# 7_Solenoid.net
KiCad netlist of a schematic drawn in Altium Designer
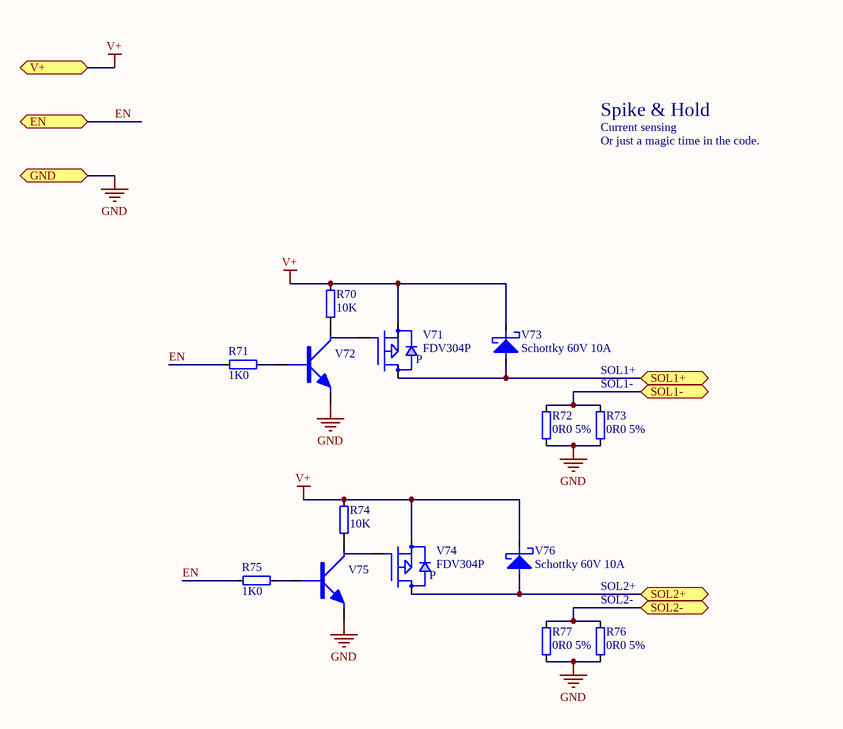
[diagram p0: 7_Solenoid.SchDoc]

(export (version "E")
  (design (tool "Eeschema 10.0.6"))
  (components
    (comp (ref "R70")
      (value "10K")
      (footprint "1206")
      (description "Resistor")
      (fields
        (field (name "MANUFACTURER") "Phycomp")
        (field (name "PARTNUMBER") "RC1206FR-0710KL")
        (field (name "CHECKEDBY") "ART")
      )
      (libsource (lib "SVN_BOMGEN_Database_2014") (part "RES"))
    )
    (comp (ref "R71")
      (value "1K0")
      (footprint "0805")
      (description "Resistor")
      (fields
        (field (name "MANUFACTURER") "Phycomp")
        (field (name "PARTNUMBER") "RC0805FR-071KL")
        (field (name "CHECKEDBY") "ART")
      )
      (libsource (lib "SVN_BOMGEN_Database_2014") (part "RES"))
    )
    (comp (ref "R72")
      (value "0R0 5%")
      (footprint "1206")
      (description "Resistor")
      (fields
        (field (name "MANUFACTURER") "Phycomp")
        (field (name "PARTNUMBER") "RC1206JR-070RL")
        (field (name "CHECKEDBY") "ART")
      )
      (libsource (lib "SVN_BOMGEN_Database_2014") (part "RES"))
    )
    (comp (ref "R73")
      (value "0R0 5%")
      (footprint "1206")
      (description "Resistor")
      (fields
        (field (name "MANUFACTURER") "Phycomp")
        (field (name "PARTNUMBER") "RC1206JR-070RL")
        (field (name "CHECKEDBY") "ART")
      )
      (libsource (lib "SVN_BOMGEN_Database_2014") (part "RES"))
    )
    (comp (ref "R74")
      (value "10K")
      (footprint "1206")
      (description "Resistor")
      (fields
        (field (name "MANUFACTURER") "Phycomp")
        (field (name "PARTNUMBER") "RC1206FR-0710KL")
        (field (name "CHECKEDBY") "ART")
      )
      (libsource (lib "SVN_BOMGEN_Database_2014") (part "RES"))
    )
    (comp (ref "R75")
      (value "1K0")
      (footprint "0805")
      (description "Resistor")
      (fields
        (field (name "MANUFACTURER") "Phycomp")
        (field (name "PARTNUMBER") "RC0805FR-071KL")
        (field (name "CHECKEDBY") "ART")
      )
      (libsource (lib "SVN_BOMGEN_Database_2014") (part "RES"))
    )
    (comp (ref "R76")
      (value "0R0 5%")
      (footprint "1206")
      (description "Resistor")
      (fields
        (field (name "MANUFACTURER") "Phycomp")
        (field (name "PARTNUMBER") "RC1206JR-070RL")
        (field (name "CHECKEDBY") "ART")
      )
      (libsource (lib "SVN_BOMGEN_Database_2014") (part "RES"))
    )
    (comp (ref "R77")
      (value "0R0 5%")
      (footprint "1206")
      (description "Resistor")
      (fields
        (field (name "MANUFACTURER") "Phycomp")
        (field (name "PARTNUMBER") "RC1206JR-070RL")
        (field (name "CHECKEDBY") "ART")
      )
      (libsource (lib "SVN_BOMGEN_Database_2014") (part "RES"))
    )
    (comp (ref "V71")
      (value "FDV304P")
      (footprint "SOT23")
      (description "MOSFET P CHANNEL GENERIC SOT23")
      (fields (field (name "MANUFACTURER") "Fairchild") (field (name "CHECKEDBY") "AJR"))
      (libsource (lib "SVN_BOMGEN_Database_2014") (part "MOSFET-P-SOT23"))
    )
    (comp (ref "V72")
      (value "BC846B")
      (footprint "SOT23")
      (description "NPN Transistor SOT23")
      (fields (field (name "MANUFACTURER") "NXP") (field (name "CHECKEDBY") "LZZ"))
      (libsource (lib "SVN_BOMGEN_Database_2014") (part "NPN-SOT23"))
    )
    (comp (ref "V73")
      (value "Schottky 60V 10A")
      (footprint "DO-214AB-DIODE")
      (description "DIODE SCHOTTKY GENERIC")
      (fields (field (name "MANUFACTURER") "Micro Commercial Co") (field (name "PARTNUMBER") "SK106-TP"))
      (libsource (lib "SVN_BOMGEN_Database_2014") (part "SCHOTTKY"))
    )
    (comp (ref "V74")
      (value "FDV304P")
      (footprint "SOT23")
      (description "MOSFET P CHANNEL GENERIC SOT23")
      (fields (field (name "MANUFACTURER") "Fairchild") (field (name "CHECKEDBY") "AJR"))
      (libsource (lib "SVN_BOMGEN_Database_2014") (part "MOSFET-P-SOT23"))
    )
    (comp (ref "V75")
      (value "BC846B")
      (footprint "SOT23")
      (description "NPN Transistor SOT23")
      (fields (field (name "MANUFACTURER") "NXP") (field (name "CHECKEDBY") "LZZ"))
      (libsource (lib "SVN_BOMGEN_Database_2014") (part "NPN-SOT23"))
    )
    (comp (ref "V76")
      (value "Schottky 60V 10A")
      (footprint "DO-214AB-DIODE")
      (description "DIODE SCHOTTKY GENERIC")
      (fields (field (name "MANUFACTURER") "Micro Commercial Co") (field (name "PARTNUMBER") "SK106-TP"))
      (libsource (lib "SVN_BOMGEN_Database_2014") (part "SCHOTTKY"))
    )
  )
  (nets
    (net (code "1") (name "/EN") (class "Default")
      (node (ref "R71") (pin "1") (pinfunction "1_1") (pintype "passive"))
      (node (ref "R75") (pin "1") (pinfunction "1_1") (pintype "passive"))
    )
    (net (code "2") (name "/SOL1+") (class "Default")
      (node (ref "V71") (pin "x") (pinfunction "d_x") (pintype "passive"))
      (node (ref "V73") (pin "a") (pinfunction "a_a") (pintype "passive"))
    )
    (net (code "3") (name "/SOL1-") (class "Default")
      (node (ref "R72") (pin "2") (pinfunction "2_2") (pintype "passive"))
      (node (ref "R73") (pin "2") (pinfunction "2_2") (pintype "passive"))
    )
    (net (code "4") (name "/SOL2+") (class "Default")
      (node (ref "V74") (pin "x") (pinfunction "d_x") (pintype "passive"))
      (node (ref "V76") (pin "a") (pinfunction "a_a") (pintype "passive"))
    )
    (net (code "5") (name "/SOL2-") (class "Default")
      (node (ref "R76") (pin "2") (pinfunction "2_2") (pintype "passive"))
      (node (ref "R77") (pin "2") (pinfunction "2_2") (pintype "passive"))
    )
    (net (code "6") (name "GND") (class "Default")
      (node (ref "R72") (pin "1") (pinfunction "1_1") (pintype "passive"))
      (node (ref "R73") (pin "1") (pinfunction "1_1") (pintype "passive"))
      (node (ref "R76") (pin "1") (pinfunction "1_1") (pintype "passive"))
      (node (ref "R77") (pin "1") (pinfunction "1_1") (pintype "passive"))
      (node (ref "V72") (pin "y") (pinfunction "Emitter_y") (pintype "passive"))
      (node (ref "V75") (pin "y") (pinfunction "Emitter_y") (pintype "passive"))
    )
    (net (code "7") (name "Net-(V72-Base)") (class "Default")
      (node (ref "R71") (pin "2") (pinfunction "2_2") (pintype "passive"))
      (node (ref "V72") (pin "z") (pinfunction "Base_z") (pintype "passive"))
    )
    (net (code "8") (name "Net-(V72-Collector)") (class "Default")
      (node (ref "R70") (pin "1") (pinfunction "1_1") (pintype "passive"))
      (node (ref "V72") (pin "x") (pinfunction "Collector_x") (pintype "passive"))
    )
    (net (code "9") (name "Net-(V75-Base)") (class "Default")
      (node (ref "R75") (pin "2") (pinfunction "2_2") (pintype "passive"))
      (node (ref "V75") (pin "z") (pinfunction "Base_z") (pintype "passive"))
    )
    (net (code "10") (name "Net-(V75-Collector)") (class "Default")
      (node (ref "R74") (pin "1") (pinfunction "1_1") (pintype "passive"))
      (node (ref "V75") (pin "x") (pinfunction "Collector_x") (pintype "passive"))
    )
    (net (code "11") (name "V+") (class "Default")
      (node (ref "R70") (pin "2") (pinfunction "2_2") (pintype "passive"))
      (node (ref "R74") (pin "2") (pinfunction "2_2") (pintype "passive"))
      (node (ref "V71") (pin "y") (pinfunction "s_y") (pintype "passive"))
      (node (ref "V73") (pin "k") (pinfunction "k_k") (pintype "passive"))
      (node (ref "V74") (pin "y") (pinfunction "s_y") (pintype "passive"))
      (node (ref "V76") (pin "k") (pinfunction "k_k") (pintype "passive"))
    )
    (net (code "12") (name "unconnected-(V71-gate-Padz)") (class "Default")
      (node (ref "V71") (pin "z") (pinfunction "gate_z") (pintype "passive"))
    )
    (net (code "13") (name "unconnected-(V74-gate-Padz)") (class "Default")
      (node (ref "V74") (pin "z") (pinfunction "gate_z") (pintype "passive"))
    )
  )
)
